# Microcontroller.net
KiCad netlist of a schematic drawn in Altium Designer
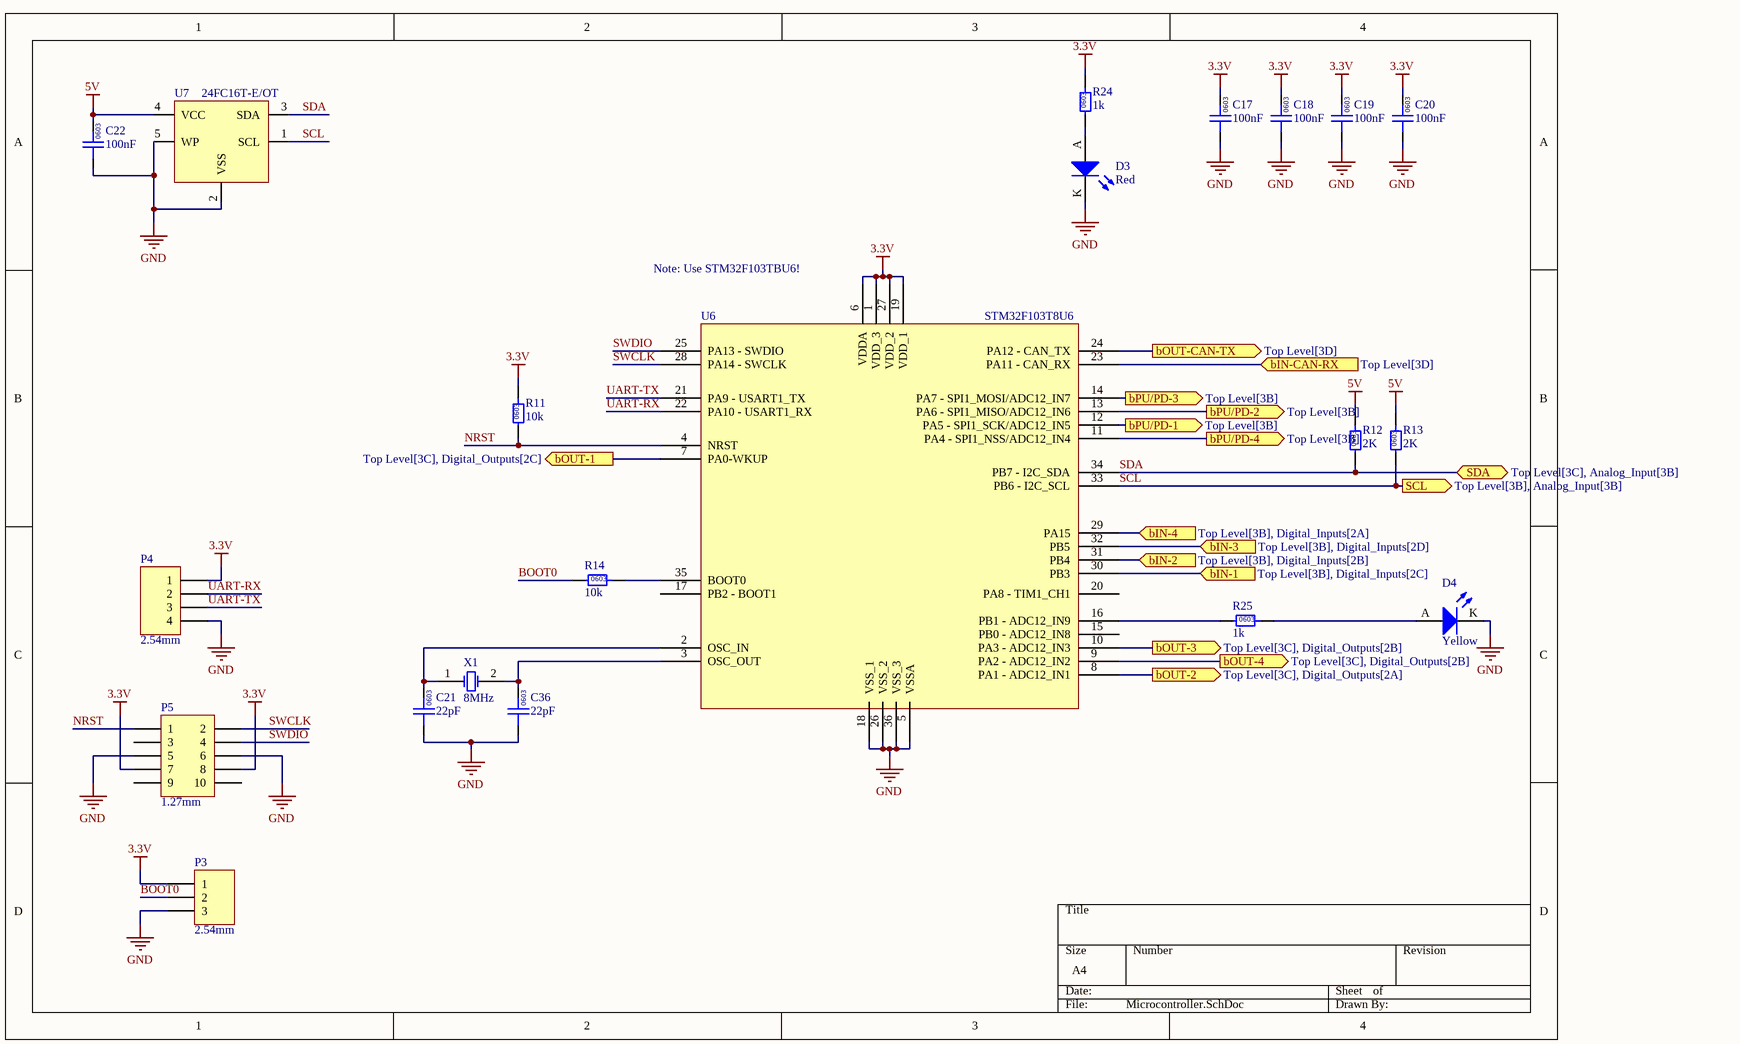
[diagram p0: Microcontroller.SchDoc]

(export (version "E")
  (design (tool "Eeschema 10.0.6"))
  (components
    (comp (ref "C17")
      (value "100nF")
      (footprint "0603")
      (fields
        (field (name "PART NUMBER") "GCM188L81H104KA57D")
        (field (name "MANUFACTURER") "muRata")
        (field (name "TOLERANCE") "±10%")
      )
      (libsource (lib "ts_standard_library") (part "Capacitor 0603"))
    )
    (comp (ref "C18")
      (value "100nF")
      (footprint "0603")
      (fields
        (field (name "PART NUMBER") "GCM188L81H104KA57D")
        (field (name "MANUFACTURER") "muRata")
        (field (name "TOLERANCE") "±10%")
      )
      (libsource (lib "ts_standard_library") (part "Capacitor 0603"))
    )
    (comp (ref "C19")
      (value "100nF")
      (footprint "0603")
      (fields
        (field (name "PART NUMBER") "GCM188L81H104KA57D")
        (field (name "MANUFACTURER") "muRata")
        (field (name "TOLERANCE") "±10%")
      )
      (libsource (lib "ts_standard_library") (part "Capacitor 0603"))
    )
    (comp (ref "C20")
      (value "100nF")
      (footprint "0603")
      (fields
        (field (name "PART NUMBER") "GCM188L81H104KA57D")
        (field (name "MANUFACTURER") "muRata")
        (field (name "TOLERANCE") "±10%")
      )
      (libsource (lib "ts_standard_library") (part "Capacitor 0603"))
    )
    (comp (ref "C21")
      (value "22pF")
      (footprint "0603")
      (fields
        (field (name "PART NUMBER") "GRM0335C1H220JA01D")
        (field (name "MANUFACTURER") "Murata Electronics")
        (field (name "TOLERANCE") "±5%")
      )
      (libsource (lib "ts_standard_library") (part "Capacitor 0603"))
    )
    (comp (ref "C22")
      (value "100nF")
      (footprint "0603")
      (fields
        (field (name "PART NUMBER") "GCM188L81H104KA57D")
        (field (name "MANUFACTURER") "muRata")
        (field (name "TOLERANCE") "±10%")
      )
      (libsource (lib "ts_standard_library") (part "Capacitor 0603"))
    )
    (comp (ref "C36")
      (value "22pF")
      (footprint "0603")
      (fields
        (field (name "PART NUMBER") "GRM0335C1H220JA01D")
        (field (name "MANUFACTURER") "Murata Electronics")
        (field (name "TOLERANCE") "±5%")
      )
      (libsource (lib "ts_standard_library") (part "Capacitor 0603"))
    )
    (comp (ref "D3")
      (value "Red")
      (footprint "0805 LED")
      (description "Red LED Indication - Discrete 1.75V 0805 (2012 Metric)")
      (fields (field (name "PART NUMBER") "SML-210LTT86") (field (name "MANUFACTURER") "ROHM Semiconductor"))
      (libsource (lib "ts_standard_library") (part "LED"))
    )
    (comp (ref "D4")
      (value "Yellow")
      (footprint "0805 LED")
      (description "Yellow LED Indication - Discrete 1.75V 0805 (2012 Metric)")
      (fields (field (name "PART NUMBER") "SML-211YTT86") (field (name "MANUFACTURER") "ROHM Semiconductor"))
      (libsource (lib "ts_standard_library") (part "LED"))
    )
    (comp (ref "P3")
      (value "2.54mm")
      (footprint "TH 2.54mm Header 1x3")
      (fields (field (name "PART NUMBER") "TH 2.54mm Header 1x3") (field (name "CONTACT") "NA"))
      (libsource (lib "ts_standard_connectors") (part "Header 1x3"))
    )
    (comp (ref "P4")
      (value "2.54mm")
      (footprint "TH 2.54mm Header 1x4")
      (fields (field (name "PART NUMBER") "TH 2.54mm Header 1x4") (field (name "CONTACT") "NA"))
      (libsource (lib "ts_standard_connectors") (part "Header 1x4"))
    )
    (comp (ref "P5")
      (value "1.27mm")
      (footprint "3221-10-0300-00")
      (fields
        (field (name "PART NUMBER") "SMD 1.27mm Header 2x5 (3221-10-0300-00)")
        (field (name "CONTACT") "NA")
      )
      (libsource (lib "ts_standard_connectors") (part "Header 2x5"))
    )
    (comp (ref "R11")
      (value "10k")
      (footprint "0603")
      (fields
        (field (name "PART NUMBER") "RC0603FR-0710KL")
        (field (name "MANUFACTURER") "YAGEO")
        (field (name "TOLERANCE") "0.01")
      )
      (libsource (lib "ts_standard_library") (part "Resistor 0603"))
    )
    (comp (ref "R12")
      (value "2K")
      (footprint "0603")
      (fields
        (field (name "PART NUMBER") "RC0603FR-072KL")
        (field (name "MANUFACTURER") "YAGEO")
        (field (name "TOLERANCE") "0.01")
      )
      (libsource (lib "ts_standard_library") (part "Resistor 0603"))
    )
    (comp (ref "R13")
      (value "2K")
      (footprint "0603")
      (fields
        (field (name "PART NUMBER") "RC0603FR-072KL")
        (field (name "MANUFACTURER") "YAGEO")
        (field (name "TOLERANCE") "0.01")
      )
      (libsource (lib "ts_standard_library") (part "Resistor 0603"))
    )
    (comp (ref "R14")
      (value "10k")
      (footprint "0603")
      (fields
        (field (name "PART NUMBER") "RC0603FR-0710KL")
        (field (name "MANUFACTURER") "YAGEO")
        (field (name "TOLERANCE") "0.01")
      )
      (libsource (lib "ts_standard_library") (part "Resistor 0603"))
    )
    (comp (ref "R24")
      (value "1k")
      (footprint "0603")
      (fields
        (field (name "PART NUMBER") "RC0603FR-071KL")
        (field (name "MANUFACTURER") "YAGEO")
        (field (name "TOLERANCE") "0.01")
      )
      (libsource (lib "ts_standard_library") (part "Resistor 0603"))
    )
    (comp (ref "R25")
      (value "1k")
      (footprint "0603")
      (fields
        (field (name "PART NUMBER") "RC0603FR-071KL")
        (field (name "MANUFACTURER") "YAGEO")
        (field (name "TOLERANCE") "0.01")
      )
      (libsource (lib "ts_standard_library") (part "Resistor 0603"))
    )
    (comp (ref "U6")
      (value "STM32F103T8U6")
      (footprint "STM_QFN-36")
      (description "ARM® Cortex®-M3 STM32F1 Microcontroller IC 32-Bit 72MHz 64KB (64K x 8) FLASH QFN")
      (fields (field (name "MANUFACTURER") "ST Microelectronics"))
      (libsource (lib "ts_standard_library") (part "STM32F103T8U6"))
    )
    (comp (ref "U7")
      (value "24FC16T-E/OT")
      (footprint "MCP SOT-23-5")
      (description "IC EEPROM 16KBIT I2C SOT23-5")
      (fields
        (field (name "MANUFACTURER") "Microchip Technology")
        (field (name "DIGIKEY PART NUMBER") "150-24FC16T-E/OTCT-ND")
      )
      (libsource (lib "ts_standard_library") (part "24FC16T-E/OT"))
    )
    (comp (ref "X1")
      (value "8MHz")
      (footprint "ECS-80-18-30-JGN-TR")
      (fields
        (field (name "PART NUMBER") "ECS-80-18-30-JGN-TR")
        (field (name "MANUFACTURER") "ECS Inc")
        (field (name "DIGIKEY PART NUMBER") "XC2103CT-ND")
      )
      (libsource (lib "ts_standard_library") (part "Crystal"))
    )
  )
  (nets
    (net (code "1") (name "/BOOT0") (class "Default")
      (node (ref "P3") (pin "2") (pinfunction "2_2") (pintype "passive"))
      (node (ref "R14") (pin "1") (pinfunction "1_1") (pintype "passive"))
    )
    (net (code "2") (name "/NRST") (class "Default")
      (node (ref "P5") (pin "1") (pinfunction "1_1") (pintype "passive"))
      (node (ref "R11") (pin "1") (pinfunction "1_1") (pintype "passive"))
      (node (ref "U6") (pin "4") (pinfunction "NRST_4") (pintype "passive"))
    )
    (net (code "3") (name "/SCL") (class "Default")
      (node (ref "R13") (pin "1") (pinfunction "1_1") (pintype "passive"))
      (node (ref "U6") (pin "33") (pinfunction "PB6_-_I2C_SCL_33") (pintype "passive"))
      (node (ref "U7") (pin "1") (pinfunction "SCL_1") (pintype "passive"))
    )
    (net (code "4") (name "/SDA") (class "Default")
      (node (ref "R12") (pin "1") (pinfunction "1_1") (pintype "passive"))
      (node (ref "U6") (pin "34") (pinfunction "PB7_-_I2C_SDA_34") (pintype "passive"))
      (node (ref "U7") (pin "3") (pinfunction "SDA_3") (pintype "passive"))
    )
    (net (code "5") (name "/SWCLK") (class "Default")
      (node (ref "P5") (pin "2") (pinfunction "2_2") (pintype "passive"))
      (node (ref "U6") (pin "28") (pinfunction "PA14_-_SWCLK_28") (pintype "passive"))
    )
    (net (code "6") (name "/SWDIO") (class "Default")
      (node (ref "P5") (pin "4") (pinfunction "4_4") (pintype "passive"))
      (node (ref "U6") (pin "25") (pinfunction "PA13_-_SWDIO_25") (pintype "passive"))
    )
    (net (code "7") (name "/UART-RX") (class "Default")
      (node (ref "P4") (pin "2") (pinfunction "2_2") (pintype "passive"))
      (node (ref "U6") (pin "22") (pinfunction "PA10_-_USART1_RX_22") (pintype "passive"))
    )
    (net (code "8") (name "/UART-TX") (class "Default")
      (node (ref "P4") (pin "3") (pinfunction "3_3") (pintype "passive"))
      (node (ref "U6") (pin "21") (pinfunction "PA9_-_USART1_TX_21") (pintype "passive"))
    )
    (net (code "9") (name "/bIN-1") (class "Default")
      (node (ref "U6") (pin "30") (pinfunction "PB3_30") (pintype "passive"))
    )
    (net (code "10") (name "/bIN-2") (class "Default")
      (node (ref "U6") (pin "31") (pinfunction "PB4_31") (pintype "passive"))
    )
    (net (code "11") (name "/bIN-3") (class "Default")
      (node (ref "U6") (pin "32") (pinfunction "PB5_32") (pintype "passive"))
    )
    (net (code "12") (name "/bIN-4") (class "Default")
      (node (ref "U6") (pin "29") (pinfunction "PA15_29") (pintype "passive"))
    )
    (net (code "13") (name "/bIN-CAN-RX") (class "Default")
      (node (ref "U6") (pin "23") (pinfunction "PA11_-_CAN_RX_23") (pintype "passive"))
    )
    (net (code "14") (name "/bOUT-1") (class "Default")
      (node (ref "U6") (pin "7") (pinfunction "PA0-WKUP_7") (pintype "passive"))
    )
    (net (code "15") (name "/bOUT-2") (class "Default")
      (node (ref "U6") (pin "8") (pinfunction "PA1_-_ADC12_IN1_8") (pintype "passive"))
    )
    (net (code "16") (name "/bOUT-3") (class "Default")
      (node (ref "U6") (pin "10") (pinfunction "PA3_-_ADC12_IN3_10") (pintype "passive"))
    )
    (net (code "17") (name "/bOUT-4") (class "Default")
      (node (ref "U6") (pin "9") (pinfunction "PA2_-_ADC12_IN2_9") (pintype "passive"))
    )
    (net (code "18") (name "/bOUT-CAN-TX") (class "Default")
      (node (ref "U6") (pin "24") (pinfunction "PA12_-_CAN_TX_24") (pintype "passive"))
    )
    (net (code "19") (name "/bPU{slash}PD-1") (class "Default")
      (node (ref "U6") (pin "12") (pinfunction "PA5_-_SPI1_SCK/ADC12_IN5_12") (pintype "passive"))
    )
    (net (code "20") (name "/bPU{slash}PD-2") (class "Default")
      (node (ref "U6") (pin "13") (pinfunction "PA6_-_SPI1_MISO/ADC12_IN6_13") (pintype "passive"))
    )
    (net (code "21") (name "/bPU{slash}PD-3") (class "Default")
      (node (ref "U6") (pin "14") (pinfunction "PA7_-_SPI1_MOSI/ADC12_IN7_14") (pintype "passive"))
    )
    (net (code "22") (name "/bPU{slash}PD-4") (class "Default")
      (node (ref "U6") (pin "11") (pinfunction "PA4_-_SPI1_NSS/ADC12_IN4_11") (pintype "passive"))
    )
    (net (code "23") (name "3.3V") (class "Default")
      (node (ref "C17") (pin "2") (pinfunction "2_2") (pintype "passive"))
      (node (ref "C18") (pin "2") (pinfunction "2_2") (pintype "passive"))
      (node (ref "C19") (pin "2") (pinfunction "2_2") (pintype "passive"))
      (node (ref "C20") (pin "2") (pinfunction "2_2") (pintype "passive"))
      (node (ref "P3") (pin "1") (pinfunction "1_1") (pintype "passive"))
      (node (ref "P4") (pin "1") (pinfunction "1_1") (pintype "passive"))
      (node (ref "P5") (pin "7") (pinfunction "7_7") (pintype "passive"))
      (node (ref "P5") (pin "8") (pinfunction "8_8") (pintype "passive"))
      (node (ref "R11") (pin "2") (pinfunction "2_2") (pintype "passive"))
      (node (ref "R24") (pin "2") (pinfunction "2_2") (pintype "passive"))
      (node (ref "U6") (pin "1") (pinfunction "VDD_3_1") (pintype "passive"))
      (node (ref "U6") (pin "19") (pinfunction "VDD_1_19") (pintype "passive"))
      (node (ref "U6") (pin "27") (pinfunction "VDD_2_27") (pintype "passive"))
      (node (ref "U6") (pin "6") (pinfunction "VDDA_6") (pintype "passive"))
    )
    (net (code "24") (name "5V") (class "Default")
      (node (ref "C22") (pin "2") (pinfunction "2_2") (pintype "passive"))
      (node (ref "R12") (pin "2") (pinfunction "2_2") (pintype "passive"))
      (node (ref "R13") (pin "2") (pinfunction "2_2") (pintype "passive"))
      (node (ref "U7") (pin "4") (pinfunction "VCC_4") (pintype "passive"))
    )
    (net (code "25") (name "GND") (class "Default")
      (node (ref "C17") (pin "1") (pinfunction "1_1") (pintype "passive"))
      (node (ref "C18") (pin "1") (pinfunction "1_1") (pintype "passive"))
      (node (ref "C19") (pin "1") (pinfunction "1_1") (pintype "passive"))
      (node (ref "C20") (pin "1") (pinfunction "1_1") (pintype "passive"))
      (node (ref "C21") (pin "1") (pinfunction "1_1") (pintype "passive"))
      (node (ref "C22") (pin "1") (pinfunction "1_1") (pintype "passive"))
      (node (ref "C36") (pin "1") (pinfunction "1_1") (pintype "passive"))
      (node (ref "D3") (pin "K") (pinfunction "K_K") (pintype "passive"))
      (node (ref "D4") (pin "K") (pinfunction "K_K") (pintype "passive"))
      (node (ref "P3") (pin "3") (pinfunction "3_3") (pintype "passive"))
      (node (ref "P4") (pin "4") (pinfunction "4_4") (pintype "passive"))
      (node (ref "P5") (pin "5") (pinfunction "5_5") (pintype "passive"))
      (node (ref "P5") (pin "6") (pinfunction "6_6") (pintype "passive"))
      (node (ref "U6") (pin "18") (pinfunction "VSS_1_18") (pintype "passive"))
      (node (ref "U6") (pin "26") (pinfunction "VSS_2_26") (pintype "passive"))
      (node (ref "U6") (pin "36") (pinfunction "VSS_3_36") (pintype "passive"))
      (node (ref "U6") (pin "5") (pinfunction "VSSA_5") (pintype "passive"))
      (node (ref "U7") (pin "2") (pinfunction "VSS_2") (pintype "passive"))
      (node (ref "U7") (pin "5") (pinfunction "WP_5") (pintype "passive"))
    )
    (net (code "26") (name "Net-(D3-PadA)") (class "Default")
      (node (ref "D3") (pin "A") (pinfunction "A_A") (pintype "passive"))
      (node (ref "R24") (pin "1") (pinfunction "1_1") (pintype "passive"))
    )
    (net (code "27") (name "Net-(D4-PadA)") (class "Default")
      (node (ref "D4") (pin "A") (pinfunction "A_A") (pintype "passive"))
      (node (ref "R25") (pin "2") (pinfunction "2_2") (pintype "passive"))
    )
    (net (code "28") (name "Net-(U6-BOOT0)") (class "Default")
      (node (ref "R14") (pin "2") (pinfunction "2_2") (pintype "passive"))
      (node (ref "U6") (pin "35") (pinfunction "BOOT0_35") (pintype "passive"))
    )
    (net (code "29") (name "Net-(U6-OSC_IN)") (class "Default")
      (node (ref "C21") (pin "2") (pinfunction "2_2") (pintype "passive"))
      (node (ref "U6") (pin "2") (pinfunction "OSC_IN_2") (pintype "passive"))
      (node (ref "X1") (pin "1") (pinfunction "OSC1_1") (pintype "passive"))
    )
    (net (code "30") (name "Net-(U6-OSC_OUT)") (class "Default")
      (node (ref "C36") (pin "2") (pinfunction "2_2") (pintype "passive"))
      (node (ref "U6") (pin "3") (pinfunction "OSC_OUT_3") (pintype "passive"))
      (node (ref "X1") (pin "2") (pinfunction "OSC2_2") (pintype "passive"))
    )
    (net (code "31") (name "Net-(U6-PB1_-_ADC12_IN9)") (class "Default")
      (node (ref "R25") (pin "1") (pinfunction "1_1") (pintype "passive"))
      (node (ref "U6") (pin "16") (pinfunction "PB1_-_ADC12_IN9_16") (pintype "passive"))
    )
    (net (code "32") (name "unconnected-(P5-Pad3)") (class "Default")
      (node (ref "P5") (pin "3") (pinfunction "3_3") (pintype "passive"))
    )
    (net (code "33") (name "unconnected-(P5-Pad9)") (class "Default")
      (node (ref "P5") (pin "9") (pinfunction "9_9") (pintype "passive"))
    )
    (net (code "34") (name "unconnected-(P5-Pad10)") (class "Default")
      (node (ref "P5") (pin "10") (pinfunction "10_10") (pintype "passive"))
    )
    (net (code "35") (name "unconnected-(U6-PA8_-_TIM1_CH1-Pad20)") (class "Default")
      (node (ref "U6") (pin "20") (pinfunction "PA8_-_TIM1_CH1_20") (pintype "passive"))
    )
    (net (code "36") (name "unconnected-(U6-PB0_-_ADC12_IN8-Pad15)") (class "Default")
      (node (ref "U6") (pin "15") (pinfunction "PB0_-_ADC12_IN8_15") (pintype "passive"))
    )
    (net (code "37") (name "unconnected-(U6-PB2_-_BOOT1-Pad17)") (class "Default")
      (node (ref "U6") (pin "17") (pinfunction "PB2_-_BOOT1_17") (pintype "passive"))
    )
  )
)
